# schematic_final_v3.net
KiCad netlist of a schematic drawn in EAGLE
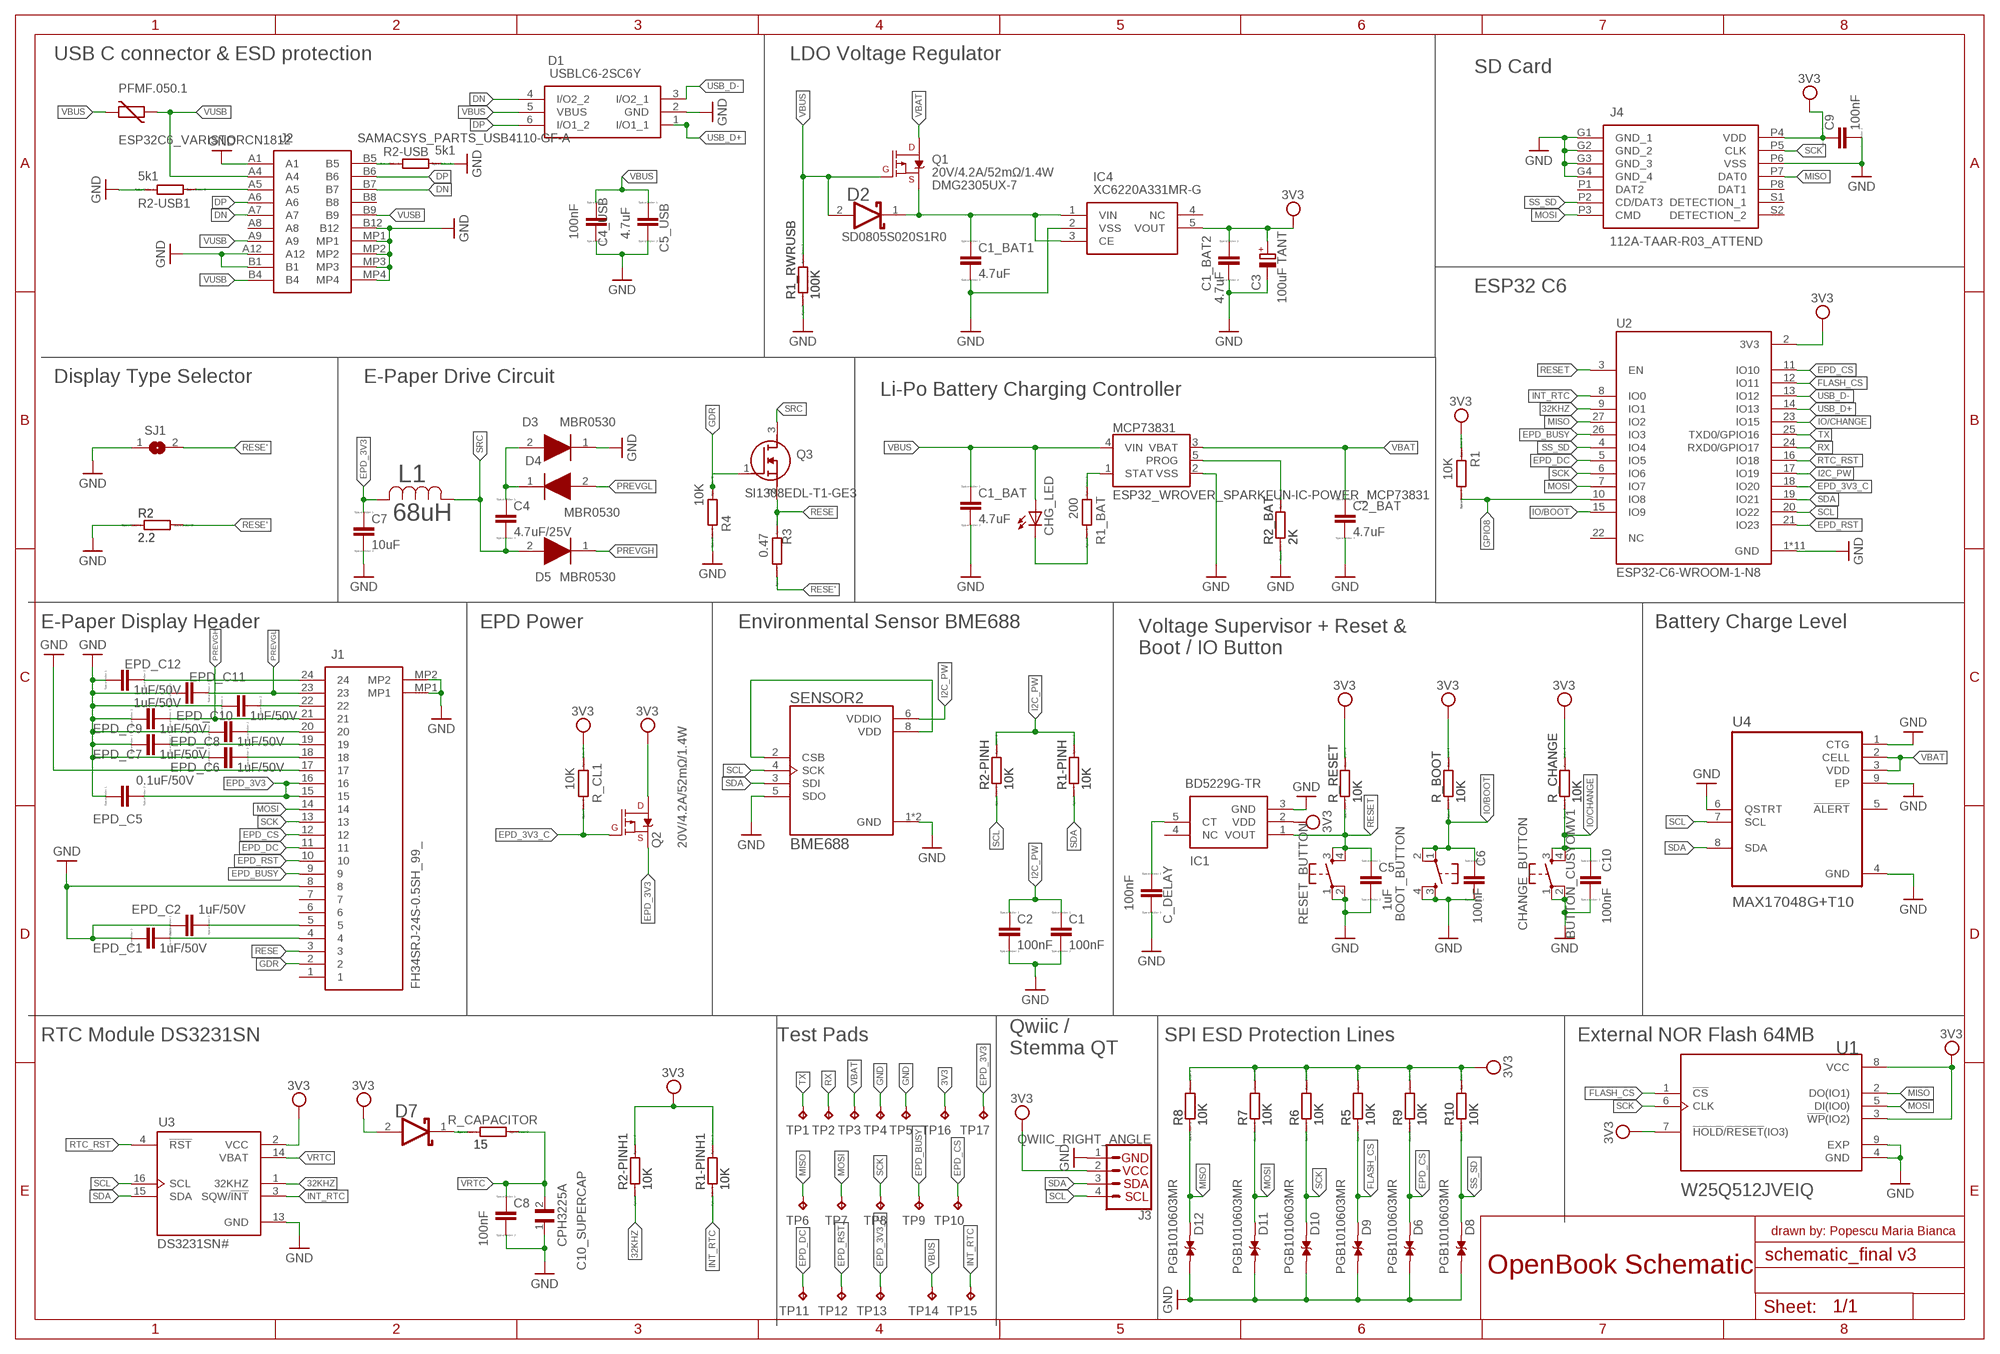
[diagram p0: schematic, sheet 1]

(export (version "E")
  (design (tool "Eeschema 10.0.6"))
  (components
    (comp (ref "BOOT_BUTTON")
      (value "BUTTON_CUSYOMV1")
      (footprint "eagle-import:MYBUTTON")
      (libsource (lib "eagle-import") (part "BUTTON_CUSYOMV1"))
    )
    (comp (ref "C1")
      (value "100nF")
      (footprint "eagle-import:EAGLE-LTSPICE_C0402")
      (libsource (lib "eagle-import") (part "EAGLE-LTSPICE_CC0402"))
    )
    (comp (ref "C1_BAT")
      (value "4.7uF")
      (footprint "eagle-import:EAGLE-LTSPICE_C0402")
      (libsource (lib "eagle-import") (part "EAGLE-LTSPICE_CC0402"))
    )
    (comp (ref "C1_BAT1")
      (value "4.7uF")
      (footprint "eagle-import:EAGLE-LTSPICE_C0402")
      (libsource (lib "eagle-import") (part "EAGLE-LTSPICE_CC0402"))
    )
    (comp (ref "C1_BAT2")
      (value "4.7uF")
      (footprint "eagle-import:EAGLE-LTSPICE_C0402")
      (libsource (lib "eagle-import") (part "EAGLE-LTSPICE_CC0402"))
    )
    (comp (ref "C2")
      (value "100nF")
      (footprint "eagle-import:EAGLE-LTSPICE_C0402")
      (libsource (lib "eagle-import") (part "EAGLE-LTSPICE_CC0402"))
    )
    (comp (ref "C2_BAT")
      (value "4.7uF")
      (footprint "eagle-import:EAGLE-LTSPICE_C0402")
      (libsource (lib "eagle-import") (part "EAGLE-LTSPICE_CC0402"))
    )
    (comp (ref "C3")
      (value "100uF TANT")
      (footprint "eagle-import:RCL_CT3528")
      (libsource (lib "eagle-import") (part "RCL_CPOL-EUCT3528"))
    )
    (comp (ref "C4")
      (value "4.7uF/25V")
      (footprint "eagle-import:EAGLE-LTSPICE_C0402")
      (libsource (lib "eagle-import") (part "EAGLE-LTSPICE_CC0402"))
    )
    (comp (ref "C4_USB")
      (value "100nF")
      (footprint "eagle-import:EAGLE-LTSPICE_C0402")
      (libsource (lib "eagle-import") (part "EAGLE-LTSPICE_CC0402"))
    )
    (comp (ref "C5")
      (value "1uF")
      (footprint "eagle-import:EAGLE-LTSPICE_C0402")
      (libsource (lib "eagle-import") (part "EAGLE-LTSPICE_CC0402"))
    )
    (comp (ref "C5_USB")
      (value "4.7uF")
      (footprint "eagle-import:EAGLE-LTSPICE_C0402")
      (libsource (lib "eagle-import") (part "EAGLE-LTSPICE_CC0402"))
    )
    (comp (ref "C6")
      (value "100nF")
      (footprint "eagle-import:EAGLE-LTSPICE_C0402")
      (libsource (lib "eagle-import") (part "EAGLE-LTSPICE_CC0402"))
    )
    (comp (ref "C7")
      (value "10uF")
      (footprint "eagle-import:EAGLE-LTSPICE_C0402")
      (libsource (lib "eagle-import") (part "EAGLE-LTSPICE_CC0402"))
    )
    (comp (ref "C8")
      (value "100nF")
      (footprint "eagle-import:EAGLE-LTSPICE_C0402")
      (libsource (lib "eagle-import") (part "EAGLE-LTSPICE_CC0402"))
    )
    (comp (ref "C9")
      (value "100nF")
      (footprint "eagle-import:EAGLE-LTSPICE_C0402")
      (libsource (lib "eagle-import") (part "EAGLE-LTSPICE_CC0402"))
    )
    (comp (ref "C10")
      (value "100nF")
      (footprint "eagle-import:EAGLE-LTSPICE_C0402")
      (libsource (lib "eagle-import") (part "EAGLE-LTSPICE_CC0402"))
    )
    (comp (ref "C10_SUPERCAP")
      (value "CPH3225A")
      (footprint "eagle-import:CAPCP3225X100N")
      (fields (field (name "MF") "Seiko Instruments"))
      (libsource (lib "eagle-import") (part "CPH3225A"))
    )
    (comp (ref "CHANGE_BUTTON")
      (value "BUTTON_CUSYOMV1")
      (footprint "eagle-import:MYBUTTON")
      (libsource (lib "eagle-import") (part "BUTTON_CUSYOMV1"))
    )
    (comp (ref "CHG_LED")
      (value "ADAFRUIT_LEDCHIP-LED0603")
      (footprint "eagle-import:ADAFRUIT_CHIP-LED0603")
      (libsource (lib "eagle-import") (part "ADAFRUIT_LEDCHIP-LED0603"))
    )
    (comp (ref "C_DELAY")
      (value "100nF")
      (footprint "eagle-import:EAGLE-LTSPICE_C0402")
      (libsource (lib "eagle-import") (part "EAGLE-LTSPICE_CC0402"))
    )
    (comp (ref "D1")
      (value "USBLC6-2SC6Y")
      (footprint "eagle-import:SOT95P280X145-6N")
      (fields (field (name "MF") "STMicroelectronics"))
      (libsource (lib "eagle-import") (part "USBLC6-2SC6Y"))
    )
    (comp (ref "D2")
      (value "SD0805S020S1R0")
      (footprint "eagle-import:ESP32_WROVER_AVX---SD0805S020S1R0_AVX_SD0805S020S1R0_0")
      (fields
        (field (name "DIGIKEY_PART_NUMBER") "478-7800-1-ND")
        (field (name "MF") "AVX")
        (field (name "MOUSER_PART_NUMBER") "581-SD0805S020S1R0")
        (field (name "ATTR") "SD0805S020S1R0")
      )
      (libsource (lib "eagle-import") (part "ESP32_WROVER_AVX---SD0805S020S1R0_AVX_SD0805S020S1R0_0_0AVX_SD0805S020S1R0_0_0"))
    )
    (comp (ref "D3")
      (value "MBR0530")
      (footprint "eagle-import:SOD3716X135N")
      (fields (field (name "MF") "ON Semiconductor"))
      (libsource (lib "eagle-import") (part "MBR0530"))
    )
    (comp (ref "D4")
      (value "MBR0530")
      (footprint "eagle-import:SOD3716X135N")
      (fields (field (name "MF") "ON Semiconductor"))
      (libsource (lib "eagle-import") (part "MBR0530"))
    )
    (comp (ref "D5")
      (value "MBR0530")
      (footprint "eagle-import:SOD3716X135N")
      (fields (field (name "MF") "ON Semiconductor"))
      (libsource (lib "eagle-import") (part "MBR0530"))
    )
    (comp (ref "D6")
      (value "PGB1010603MR")
      (footprint "eagle-import:DIOC1608X36N")
      (fields (field (name "MF") "Littelfuse Inc."))
      (libsource (lib "eagle-import") (part "PGB1010603MR"))
    )
    (comp (ref "D7")
      (value "ESP32_WROVER_AVX---SD0805S020S1R0_AVX_SD0805S020S1R0_0_0AVX_SD0805S020S1R0_0_0")
      (footprint "eagle-import:ESP32_WROVER_AVX---SD0805S020S1R0_AVX_SD0805S020S1R0_0")
      (fields
        (field (name "DIGIKEY_PART_NUMBER") "478-7800-1-ND")
        (field (name "MF") "AVX")
        (field (name "MOUSER_PART_NUMBER") "581-SD0805S020S1R0")
      )
      (libsource (lib "eagle-import") (part "ESP32_WROVER_AVX---SD0805S020S1R0_AVX_SD0805S020S1R0_0_0AVX_SD0805S020S1R0_0_0"))
    )
    (comp (ref "D8")
      (value "PGB1010603MR")
      (footprint "eagle-import:DIOC1608X36N")
      (fields (field (name "MF") "Littelfuse Inc."))
      (libsource (lib "eagle-import") (part "PGB1010603MR"))
    )
    (comp (ref "D9")
      (value "PGB1010603MR")
      (footprint "eagle-import:DIOC1608X36N")
      (fields (field (name "MF") "Littelfuse Inc."))
      (libsource (lib "eagle-import") (part "PGB1010603MR"))
    )
    (comp (ref "D10")
      (value "PGB1010603MR")
      (footprint "eagle-import:DIOC1608X36N")
      (fields (field (name "MF") "Littelfuse Inc."))
      (libsource (lib "eagle-import") (part "PGB1010603MR"))
    )
    (comp (ref "D11")
      (value "PGB1010603MR")
      (footprint "eagle-import:DIOC1608X36N")
      (fields (field (name "MF") "Littelfuse Inc."))
      (libsource (lib "eagle-import") (part "PGB1010603MR"))
    )
    (comp (ref "D12")
      (value "PGB1010603MR")
      (footprint "eagle-import:DIOC1608X36N")
      (fields (field (name "MF") "Littelfuse Inc."))
      (libsource (lib "eagle-import") (part "PGB1010603MR"))
    )
    (comp (ref "EPD_C1")
      (value "1uF/50V")
      (footprint "eagle-import:EAGLE-LTSPICE_C0402")
      (libsource (lib "eagle-import") (part "EAGLE-LTSPICE_CC0402"))
    )
    (comp (ref "EPD_C2")
      (value "1uF/50V")
      (footprint "eagle-import:EAGLE-LTSPICE_C0402")
      (libsource (lib "eagle-import") (part "EAGLE-LTSPICE_CC0402"))
    )
    (comp (ref "EPD_C5")
      (value "0.1uF/50V")
      (footprint "eagle-import:EAGLE-LTSPICE_C0402")
      (libsource (lib "eagle-import") (part "EAGLE-LTSPICE_CC0402"))
    )
    (comp (ref "EPD_C6")
      (value "1uF/50V")
      (footprint "eagle-import:EAGLE-LTSPICE_C0402")
      (libsource (lib "eagle-import") (part "EAGLE-LTSPICE_CC0402"))
    )
    (comp (ref "EPD_C7")
      (value "1uF/50V")
      (footprint "eagle-import:EAGLE-LTSPICE_C0402")
      (libsource (lib "eagle-import") (part "EAGLE-LTSPICE_CC0402"))
    )
    (comp (ref "EPD_C8")
      (value "1uF/50V")
      (footprint "eagle-import:EAGLE-LTSPICE_C0402")
      (libsource (lib "eagle-import") (part "EAGLE-LTSPICE_CC0402"))
    )
    (comp (ref "EPD_C9")
      (value "1uF/50V")
      (footprint "eagle-import:EAGLE-LTSPICE_C0402")
      (libsource (lib "eagle-import") (part "EAGLE-LTSPICE_CC0402"))
    )
    (comp (ref "EPD_C10")
      (value "1uF/50V")
      (footprint "eagle-import:EAGLE-LTSPICE_C0402")
      (libsource (lib "eagle-import") (part "EAGLE-LTSPICE_CC0402"))
    )
    (comp (ref "EPD_C11")
      (value "1uF/50V")
      (footprint "eagle-import:EAGLE-LTSPICE_C0402")
      (libsource (lib "eagle-import") (part "EAGLE-LTSPICE_CC0402"))
    )
    (comp (ref "EPD_C12")
      (value "1uF/50V")
      (footprint "eagle-import:EAGLE-LTSPICE_C0402")
      (libsource (lib "eagle-import") (part "EAGLE-LTSPICE_CC0402"))
    )
    (comp (ref "IC1")
      (value "BD5229G-TR")
      (footprint "eagle-import:SOT95P280X125-5N")
      (fields (field (name "MOUSER_PART_NUMBER") "755-BD5229G-TR"))
      (libsource (lib "eagle-import") (part "BD5229G-TR"))
    )
    (comp (ref "IC4")
      (value "XC6220A331MR-G")
      (footprint "eagle-import:SOT95P280X120-5N")
      (fields (field (name "MOUSER_PART_NUMBER") "865-XC6220A331MR-G"))
      (libsource (lib "eagle-import") (part "XC6220A331MR-G"))
    )
    (comp (ref "J1")
      (value "FH34SRJ-24S-0.5SH_99_")
      (footprint "eagle-import:FH34SRJ24S05SH99")
      (fields
        (field (name "MANUFACTURER_PART_NUMBER") "FH34SRJ-24S-0.5SH(99)")
        (field (name "MOUSER_PART_NUMBER") "798-FH34SRJ24S05SH99")
      )
      (libsource (lib "eagle-import") (part "FH34SRJ-24S-0.5SH_99_"))
    )
    (comp (ref "J2")
      (value "SAMACSYS_PARTS_USB4110-GF-A")
      (footprint "eagle-import:SAMACSYS_PARTS_USB4110GFA")
      (fields
        (field (name "MANUFACTURER_PART_NUMBER") "USB4110-GF-A")
        (field (name "MOUSER_PART_NUMBER") "640-USB4110-GF-A")
      )
      (libsource (lib "eagle-import") (part "SAMACSYS_PARTS_USB4110-GF-A"))
    )
    (comp (ref "J3")
      (value "QWIIC_RIGHT_ANGLE")
      (footprint "eagle-import:JST04_1MM_RA")
      (libsource (lib "eagle-import") (part "QWIIC_CONNECTORJS-1MM"))
    )
    (comp (ref "J4")
      (value "112A-TAAR-R03_ATTEND")
      (footprint "eagle-import:112ATAARR03ATTEND")
      (fields (field (name "MANUFACTURER_PART_NUMBER") "112A-TAAR-R03 ATTEND"))
      (libsource (lib "eagle-import") (part "112A-TAAR-R03_ATTEND"))
    )
    (comp (ref "L1")
      (value "68uH")
      (footprint "eagle-import:IND_4828-WE-TPC_WRE")
      (fields
        (field (name "MANUFACTURER_PART_NUMBER") "744043680")
        (field (name "COPYRIGHT") "Copyright (C) 2024 Ultra Librarian. All rights reserved.")
      )
      (libsource (lib "eagle-import") (part "744043680IND_4828-WE-TPC_WRE"))
    )
    (comp (ref "MCP73831")
      (value "ESP32_WROVER_SPARKFUN-IC-POWER_MCP73831")
      (footprint "eagle-import:ESP32_WROVER_SPARKFUN-IC-POWER_SOT23-5")
      (libsource (lib "eagle-import") (part "ESP32_WROVER_SPARKFUN-IC-POWER_MCP73831"))
    )
    (comp (ref "PFMF.050.1")
      (value "ESP32C6_VARISTORCN1812")
      (footprint "eagle-import:ESP32C6_VARISTOR_CT_CN1812")
      (libsource (lib "eagle-import") (part "ESP32C6_VARISTORCN1812"))
    )
    (comp (ref "Q1")
      (value "20V/4.2A/52mΩ/1.4W")
      (footprint "eagle-import:ESP32_WROVER_SPARKFUN-DISCRETESEMI_SOT23-3")
      (fields (field (name "ATTR") "DMG2305UX-7"))
      (libsource (lib "eagle-import") (part "ESP32_WROVER_SPARKFUN-DISCRETESEMI_MOSFET_PCH-DMG2305UX-7"))
    )
    (comp (ref "Q2")
      (value "20V/4.2A/52mΩ/1.4W")
      (footprint "eagle-import:ESP32_WROVER_SPARKFUN-DISCRETESEMI_SOT23-3")
      (libsource (lib "eagle-import") (part "ESP32_WROVER_SPARKFUN-DISCRETESEMI_MOSFET_PCH-DMG2305UX-7"))
    )
    (comp (ref "Q3")
      (value "SI1308EDL-T1-GE3")
      (footprint "eagle-import:SOT65P210X110-3N")
      (fields (field (name "MF") "Vishay Siliconix"))
      (libsource (lib "eagle-import") (part "SI1308EDL-T1-GE3"))
    )
    (comp (ref "R1")
      (value "10K")
      (footprint "eagle-import:ESP32_WROVER_EAGLE-LTSPICE_R0402")
      (libsource (lib "eagle-import") (part "ESP32_WROVER_EAGLE-LTSPICE_RR0402"))
    )
    (comp (ref "R1-PINH")
      (value "10K")
      (footprint "eagle-import:ESP32_WROVER_EAGLE-LTSPICE_R0402")
      (libsource (lib "eagle-import") (part "ESP32_WROVER_EAGLE-LTSPICE_RR0402"))
    )
    (comp (ref "R1-PINH1")
      (value "10K")
      (footprint "eagle-import:ESP32_WROVER_EAGLE-LTSPICE_R0402")
      (libsource (lib "eagle-import") (part "ESP32_WROVER_EAGLE-LTSPICE_RR0402"))
    )
    (comp (ref "R1_BAT")
      (value "200")
      (footprint "eagle-import:ESP32_WROVER_EAGLE-LTSPICE_R0402")
      (libsource (lib "eagle-import") (part "ESP32_WROVER_EAGLE-LTSPICE_RR0402"))
    )
    (comp (ref "R1_RWRUSB")
      (value "100K")
      (footprint "eagle-import:ESP32_WROVER_EAGLE-LTSPICE_R0402")
      (libsource (lib "eagle-import") (part "ESP32_WROVER_EAGLE-LTSPICE_RR0402"))
    )
    (comp (ref "R2")
      (value "2.2")
      (footprint "eagle-import:ESP32_WROVER_EAGLE-LTSPICE_R0402")
      (libsource (lib "eagle-import") (part "ESP32_WROVER_EAGLE-LTSPICE_RR0402"))
    )
    (comp (ref "R2-PINH")
      (value "10K")
      (footprint "eagle-import:ESP32_WROVER_EAGLE-LTSPICE_R0402")
      (libsource (lib "eagle-import") (part "ESP32_WROVER_EAGLE-LTSPICE_RR0402"))
    )
    (comp (ref "R2-PINH1")
      (value "10K")
      (footprint "eagle-import:ESP32_WROVER_EAGLE-LTSPICE_R0402")
      (libsource (lib "eagle-import") (part "ESP32_WROVER_EAGLE-LTSPICE_RR0402"))
    )
    (comp (ref "R2-USB")
      (value "5k1")
      (footprint "eagle-import:ESP32_WROVER_EAGLE-LTSPICE_R0402")
      (libsource (lib "eagle-import") (part "ESP32_WROVER_EAGLE-LTSPICE_RR0402"))
    )
    (comp (ref "R2-USB1")
      (value "5k1")
      (footprint "eagle-import:ESP32_WROVER_EAGLE-LTSPICE_R0402")
      (libsource (lib "eagle-import") (part "ESP32_WROVER_EAGLE-LTSPICE_RR0402"))
    )
    (comp (ref "R2_BAT")
      (value "2K")
      (footprint "eagle-import:ESP32_WROVER_EAGLE-LTSPICE_R0402")
      (libsource (lib "eagle-import") (part "ESP32_WROVER_EAGLE-LTSPICE_RR0402"))
    )
    (comp (ref "R3")
      (value "0.47")
      (footprint "eagle-import:ESP32_WROVER_EAGLE-LTSPICE_R0402")
      (libsource (lib "eagle-import") (part "ESP32_WROVER_EAGLE-LTSPICE_RR0402"))
    )
    (comp (ref "R4")
      (value "10K")
      (footprint "eagle-import:ESP32_WROVER_EAGLE-LTSPICE_R0402")
      (libsource (lib "eagle-import") (part "ESP32_WROVER_EAGLE-LTSPICE_RR0402"))
    )
    (comp (ref "R5")
      (value "10K")
      (footprint "eagle-import:ESP32_WROVER_EAGLE-LTSPICE_R0402")
      (libsource (lib "eagle-import") (part "ESP32_WROVER_EAGLE-LTSPICE_RR0402"))
    )
    (comp (ref "R6")
      (value "10K")
      (footprint "eagle-import:ESP32_WROVER_EAGLE-LTSPICE_R0402")
      (libsource (lib "eagle-import") (part "ESP32_WROVER_EAGLE-LTSPICE_RR0402"))
    )
    (comp (ref "R7")
      (value "10K")
      (footprint "eagle-import:ESP32_WROVER_EAGLE-LTSPICE_R0402")
      (libsource (lib "eagle-import") (part "ESP32_WROVER_EAGLE-LTSPICE_RR0402"))
    )
    (comp (ref "R8")
      (value "10K")
      (footprint "eagle-import:ESP32_WROVER_EAGLE-LTSPICE_R0402")
      (libsource (lib "eagle-import") (part "ESP32_WROVER_EAGLE-LTSPICE_RR0402"))
    )
    (comp (ref "R9")
      (value "10K")
      (footprint "eagle-import:ESP32_WROVER_EAGLE-LTSPICE_R0402")
      (libsource (lib "eagle-import") (part "ESP32_WROVER_EAGLE-LTSPICE_RR0402"))
    )
    (comp (ref "R10")
      (value "10K")
      (footprint "eagle-import:ESP32_WROVER_EAGLE-LTSPICE_R0402")
      (libsource (lib "eagle-import") (part "ESP32_WROVER_EAGLE-LTSPICE_RR0402"))
    )
    (comp (ref "RESET_BUTTON")
      (value "RESET_BUTTON")
      (footprint "eagle-import:MYBUTTON")
      (libsource (lib "eagle-import") (part "BUTTON_CUSYOMV1"))
    )
    (comp (ref "R_BOOT")
      (value "10K")
      (footprint "eagle-import:ESP32_WROVER_EAGLE-LTSPICE_R0402")
      (libsource (lib "eagle-import") (part "ESP32_WROVER_EAGLE-LTSPICE_RR0402"))
    )
    (comp (ref "R_CAPACITOR")
      (value "15")
      (footprint "eagle-import:ESP32_WROVER_EAGLE-LTSPICE_R0402")
      (libsource (lib "eagle-import") (part "ESP32_WROVER_EAGLE-LTSPICE_RR0402"))
    )
    (comp (ref "R_CHANGE")
      (value "10K")
      (footprint "eagle-import:ESP32_WROVER_EAGLE-LTSPICE_R0402")
      (libsource (lib "eagle-import") (part "ESP32_WROVER_EAGLE-LTSPICE_RR0402"))
    )
    (comp (ref "R_CL1")
      (value "10K")
      (footprint "eagle-import:ESP32_WROVER_EAGLE-LTSPICE_R0402")
      (libsource (lib "eagle-import") (part "ESP32_WROVER_EAGLE-LTSPICE_RR0402"))
    )
    (comp (ref "R_RESET")
      (value "10K")
      (footprint "eagle-import:ESP32_WROVER_EAGLE-LTSPICE_R0402")
      (libsource (lib "eagle-import") (part "ESP32_WROVER_EAGLE-LTSPICE_RR0402"))
    )
    (comp (ref "SENSOR2")
      (value "BME688")
      (footprint "eagle-import:ESP32_WROVER_BME680_PSON80P300X300X100-8N")
      (fields (field (name "MF") "Bosch Sensortec") (field (name "MP") "BME680"))
      (libsource (lib "eagle-import") (part "ESP32_WROVER_BME680_BME680"))
    )
    (comp (ref "SJ1") (value "SJ") (footprint "eagle-import:SJ") (libsource (lib "eagle-import") (part "SJ")))
    (comp (ref "TP1")
      (value "TPTP20R")
      (footprint "eagle-import:TP20R")
      (libsource (lib "eagle-import") (part "TPTP20R"))
    )
    (comp (ref "TP2")
      (value "TPTP20R")
      (footprint "eagle-import:TP20R")
      (libsource (lib "eagle-import") (part "TPTP20R"))
    )
    (comp (ref "TP3")
      (value "TPTP20R")
      (footprint "eagle-import:TP20R")
      (libsource (lib "eagle-import") (part "TPTP20R"))
    )
    (comp (ref "TP4")
      (value "TPTP20R")
      (footprint "eagle-import:TP20R")
      (libsource (lib "eagle-import") (part "TPTP20R"))
    )
    (comp (ref "TP5")
      (value "TPTP20R")
      (footprint "eagle-import:TP20R")
      (libsource (lib "eagle-import") (part "TPTP20R"))
    )
    (comp (ref "TP6")
      (value "TPTP20R")
      (footprint "eagle-import:TP20R")
      (libsource (lib "eagle-import") (part "TPTP20R"))
    )
    (comp (ref "TP7")
      (value "TPTP20R")
      (footprint "eagle-import:TP20R")
      (libsource (lib "eagle-import") (part "TPTP20R"))
    )
    (comp (ref "TP8")
      (value "TPTP20R")
      (footprint "eagle-import:TP20R")
      (libsource (lib "eagle-import") (part "TPTP20R"))
    )
    (comp (ref "TP9")
      (value "TPTP20R")
      (footprint "eagle-import:TP20R")
      (libsource (lib "eagle-import") (part "TPTP20R"))
    )
    (comp (ref "TP10")
      (value "TPTP20R")
      (footprint "eagle-import:TP20R")
      (libsource (lib "eagle-import") (part "TPTP20R"))
    )
    (comp (ref "TP11")
      (value "TPTP20R")
      (footprint "eagle-import:TP20R")
      (libsource (lib "eagle-import") (part "TPTP20R"))
    )
    (comp (ref "TP12")
      (value "TPTP20R")
      (footprint "eagle-import:TP20R")
      (libsource (lib "eagle-import") (part "TPTP20R"))
    )
    (comp (ref "TP13")
      (value "TPTP20R")
      (footprint "eagle-import:TP20R")
      (libsource (lib "eagle-import") (part "TPTP20R"))
    )
    (comp (ref "TP14")
      (value "TPTP20R")
      (footprint "eagle-import:TP20R")
      (libsource (lib "eagle-import") (part "TPTP20R"))
    )
    (comp (ref "TP15")
      (value "TPTP20R")
      (footprint "eagle-import:TP20R")
      (libsource (lib "eagle-import") (part "TPTP20R"))
    )
    (comp (ref "TP16")
      (value "TPTP20R")
      (footprint "eagle-import:TP20R")
      (libsource (lib "eagle-import") (part "TPTP20R"))
    )
    (comp (ref "TP17")
      (value "TPTP20R")
      (footprint "eagle-import:TP20R")
      (libsource (lib "eagle-import") (part "TPTP20R"))
    )
    (comp (ref "U1")
      (value "W25Q512JVEIQ")
      (footprint "eagle-import:SON127P600X800X80-9N")
      (fields (field (name "MF") "Winbond Electronics"))
      (libsource (lib "eagle-import") (part "W25Q512JVEIQ"))
    )
    (comp (ref "U2")
      (value "ESP32-C6-WROOM-1-N8")
      (footprint "eagle-import:XCVR_ESP32-C6-WROOM-1-N8")
      (fields (field (name "MF") "Espressif Systems"))
      (libsource (lib "eagle-import") (part "ESP32-C6-WROOM-1-N8"))
    )
    (comp (ref "U3")
      (value "DS3231SN#")
      (footprint "eagle-import:SOIC127P1032X265-16N")
      (fields (field (name "MF") "Analog Devices"))
      (libsource (lib "eagle-import") (part "DS3231SN#"))
    )
    (comp (ref "U4")
      (value "MAX17048G+T10")
      (footprint "eagle-import:SON50P200X200X80-9N")
      (fields (field (name "MF") "Analog Devices"))
      (libsource (lib "eagle-import") (part "MAX17048G+T10"))
    )
  )
  (nets
    (net (code "1") (name "3V3") (class "Default")
      (node (ref "C1_BAT2") (pin "1") (pinfunction "1_1") (pintype "passive"))
      (node (ref "C3") (pin "+") (pinfunction "+_+") (pintype "passive"))
      (node (ref "C9") (pin "1") (pinfunction "1_1") (pintype "passive"))
      (node (ref "D7") (pin "2") (pinfunction "ANODE_2") (pintype "bidirectional"))
      (node (ref "IC1") (pin "2") (pinfunction "VDD_2") (pintype "bidirectional"))
      (node (ref "IC4") (pin "5") (pinfunction "VOUT_5") (pintype "bidirectional"))
      (node (ref "J3") (pin "2") (pinfunction "2_2") (pintype "power_in"))
      (node (ref "J4") (pin "P4") (pinfunction "VDD_P4") (pintype "bidirectional"))
      (node (ref "Q2") (pin "3") (pinfunction "D_3") (pintype "bidirectional"))
      (node (ref "R1") (pin "2") (pinfunction "2_2") (pintype "passive"))
      (node (ref "R1-PINH1") (pin "2") (pinfunction "2_2") (pintype "passive"))
      (node (ref "R10") (pin "2") (pinfunction "2_2") (pintype "passive"))
      (node (ref "R2-PINH1") (pin "2") (pinfunction "2_2") (pintype "passive"))
      (node (ref "R5") (pin "2") (pinfunction "2_2") (pintype "passive"))
      (node (ref "R6") (pin "2") (pinfunction "2_2") (pintype "passive"))
      (node (ref "R7") (pin "2") (pinfunction "2_2") (pintype "passive"))
      (node (ref "R8") (pin "2") (pinfunction "2_2") (pintype "passive"))
      (node (ref "R9") (pin "2") (pinfunction "2_2") (pintype "passive"))
      (node (ref "R_BOOT") (pin "2") (pinfunction "2_2") (pintype "passive"))
      (node (ref "R_CHANGE") (pin "2") (pinfunction "2_2") (pintype "passive"))
      (node (ref "R_CL1") (pin "2") (pinfunction "2_2") (pintype "passive"))
      (node (ref "R_RESET") (pin "2") (pinfunction "2_2") (pintype "passive"))
      (node (ref "TP16") (pin "TP") (pinfunction "TP_TP") (pintype "input"))
      (node (ref "U1") (pin "3") (pinfunction "~{WP}(IO2)_3") (pintype "bidirectional"))
      (node (ref "U1") (pin "7") (pinfunction "~{HOLD}/~{RESET}(IO3)_7") (pintype "bidirectional"))
      (node (ref "U1") (pin "8") (pinfunction "VCC_8") (pintype "power_in"))
      (node (ref "U2") (pin "2") (pinfunction "3V3_2") (pintype "power_in"))
      (node (ref "U3") (pin "2") (pinfunction "VCC_2") (pintype "power_in"))
    )
    (net (code "2") (name "32KHZ") (class "Default")
      (node (ref "R2-PINH1") (pin "1") (pinfunction "1_1") (pintype "passive"))
      (node (ref "U2") (pin "9") (pinfunction "IO1_9") (pintype "bidirectional"))
      (node (ref "U3") (pin "1") (pinfunction "32KHZ_1") (pintype "output"))
    )
    (net (code "3") (name "DN") (class "Default")
      (node (ref "D1") (pin "4") (pinfunction "I/O2_2_4") (pintype "bidirectional"))
      (node (ref "J2") (pin "A7") (pinfunction "A7_A7") (pintype "bidirectional"))
      (node (ref "J2") (pin "B7") (pinfunction "B7_B7") (pintype "bidirectional"))
    )
    (net (code "4") (name "DP") (class "Default")
      (node (ref "D1") (pin "6") (pinfunction "I/O1_2_6") (pintype "bidirectional"))
      (node (ref "J2") (pin "A6") (pinfunction "A6_A6") (pintype "bidirectional"))
      (node (ref "J2") (pin "B6") (pinfunction "B6_B6") (pintype "bidirectional"))
    )
    (net (code "5") (name "EPD_3V3") (class "Default")
      (node (ref "C7") (pin "1") (pinfunction "1_1") (pintype "passive"))
      (node (ref "EPD_C5") (pin "2") (pinfunction "2_2") (pintype "passive"))
      (node (ref "J1") (pin "15") (pinfunction "15_15") (pintype "bidirectional"))
      (node (ref "J1") (pin "16") (pinfunction "16_16") (pintype "bidirectional"))
      (node (ref "L1") (pin "2") (pinfunction "2_2") (pintype "passive"))
      (node (ref "Q2") (pin "2") (pinfunction "S_2") (pintype "bidirectional"))
      (node (ref "TP17") (pin "TP") (pinfunction "TP_TP") (pintype "input"))
    )
    (net (code "6") (name "EPD_3V3_C") (class "Default")
      (node (ref "Q2") (pin "1") (pinfunction "G_1") (pintype "bidirectional"))
      (node (ref "R_CL1") (pin "1") (pinfunction "1_1") (pintype "passive"))
      (node (ref "TP13") (pin "TP") (pinfunction "TP_TP") (pintype "input"))
      (node (ref "U2") (pin "18") (pinfunction "IO20_18") (pintype "bidirectional"))
    )
    (net (code "7") (name "EPD_BUSY") (class "Default")
      (node (ref "J1") (pin "9") (pinfunction "9_9") (pintype "bidirectional"))
      (node (ref "TP9") (pin "TP") (pinfunction "TP_TP") (pintype "input"))
      (node (ref "U2") (pin "26") (pinfunction "IO3_26") (pintype "bidirectional"))
    )
    (net (code "8") (name "EPD_CS") (class "Default")
      (node (ref "D6") (pin "2") (pinfunction "2_2") (pintype "passive"))
      (node (ref "J1") (pin "12") (pinfunction "12_12") (pintype "bidirectional"))
      (node (ref "R9") (pin "1") (pinfunction "1_1") (pintype "passive"))
      (node (ref "TP10") (pin "TP") (pinfunction "TP_TP") (pintype "input"))
      (node (ref "U2") (pin "11") (pinfunction "IO10_11") (pintype "bidirectional"))
    )
    (net (code "9") (name "EPD_DC") (class "Default")
      (node (ref "J1") (pin "11") (pinfunction "11_11") (pintype "bidirectional"))
      (node (ref "TP11") (pin "TP") (pinfunction "TP_TP") (pintype "input"))
      (node (ref "U2") (pin "5") (pinfunction "IO5_5") (pintype "bidirectional"))
    )
    (net (code "10") (name "EPD_RST") (class "Default")
      (node (ref "J1") (pin "10") (pinfunction "10_10") (pintype "bidirectional"))
      (node (ref "TP12") (pin "TP") (pinfunction "TP_TP") (pintype "input"))
      (node (ref "U2") (pin "21") (pinfunction "IO23_21") (pintype "bidirectional"))
    )
    (net (code "11") (name "FLASH_CS") (class "Default")
      (node (ref "D9") (pin "2") (pinfunction "2_2") (pintype "passive"))
      (node (ref "R5") (pin "1") (pinfunction "1_1") (pintype "passive"))
      (node (ref "U1") (pin "1") (pinfunction "~{CS}_1") (pintype "input"))
      (node (ref "U2") (pin "12") (pinfunction "IO11_12") (pintype "bidirectional"))
    )
    (net (code "12") (name "GDR") (class "Default")
      (node (ref "J1") (pin "2") (pinfunction "2_2") (pintype "bidirectional"))
      (node (ref "Q3") (pin "1") (pinfunction "G_1") (pintype "bidirectional"))
      (node (ref "R4") (pin "2") (pinfunction "2_2") (pintype "passive"))
    )
    (net (code "13") (name "GND") (class "Default")
      (node (ref "BOOT_BUTTON") (pin "3") (pinfunction "3_3") (pintype "passive"))
      (node (ref "BOOT_BUTTON") (pin "4") (pinfunction "4_4") (pintype "passive"))
      (node (ref "C1") (pin "2") (pinfunction "2_2") (pintype "passive"))
      (node (ref "C10") (pin "2") (pinfunction "2_2") (pintype "passive"))
      (node (ref "C10_SUPERCAP") (pin "1") (pinfunction "1_1") (pintype "passive"))
      (node (ref "C1_BAT") (pin "2") (pinfunction "2_2") (pintype "passive"))
      (node (ref "C1_BAT1") (pin "2") (pinfunction "2_2") (pintype "passive"))
      (node (ref "C1_BAT2") (pin "2") (pinfunction "2_2") (pintype "passive"))
      (node (ref "C2") (pin "2") (pinfunction "2_2") (pintype "passive"))
      (node (ref "C2_BAT") (pin "2") (pinfunction "2_2") (pintype "passive"))
      (node (ref "C3") (pin "-") (pinfunction "-_-") (pintype "passive"))
      (node (ref "C4_USB") (pin "2") (pinfunction "2_2") (pintype "passive"))
      (node (ref "C5") (pin "2") (pinfunction "2_2") (pintype "passive"))
      (node (ref "C5_USB") (pin "2") (pinfunction "2_2") (pintype "passive"))
      (node (ref "C6") (pin "2") (pinfunction "2_2") (pintype "passive"))
      (node (ref "C7") (pin "2") (pinfunction "2_2") (pintype "passive"))
      (node (ref "C8") (pin "2") (pinfunction "2_2") (pintype "passive"))
      (node (ref "C9") (pin "2") (pinfunction "2_2") (pintype "passive"))
      (node (ref "CHANGE_BUTTON") (pin "1") (pinfunction "1_1") (pintype "passive"))
      (node (ref "CHANGE_BUTTON") (pin "2") (pinfunction "2_2") (pintype "passive"))
      (node (ref "C_DELAY") (pin "2") (pinfunction "2_2") (pintype "passive"))
      (node (ref "D1") (pin "2") (pinfunction "GND_2") (pintype "bidirectional"))
      (node (ref "D10") (pin "1") (pinfunction "1_1") (pintype "passive"))
      (node (ref "D11") (pin "1") (pinfunction "1_1") (pintype "passive"))
      (node (ref "D12") (pin "1") (pinfunction "1_1") (pintype "passive"))
      (node (ref "D3") (pin "1") (pinfunction "K_1") (pintype "bidirectional"))
      (node (ref "D6") (pin "1") (pinfunction "1_1") (pintype "passive"))
      (node (ref "D8") (pin "1") (pinfunction "1_1") (pintype "passive"))
      (node (ref "D9") (pin "1") (pinfunction "1_1") (pintype "passive"))
      (node (ref "EPD_C1") (pin "1") (pinfunction "1_1") (pintype "passive"))
      (node (ref "EPD_C10") (pin "1") (pinfunction "1_1") (pintype "passive"))
      (node (ref "EPD_C11") (pin "1") (pinfunction "1_1") (pintype "passive"))
      (node (ref "EPD_C12") (pin "1") (pinfunction "1_1") (pintype "passive"))
      (node (ref "EPD_C2") (pin "1") (pinfunction "1_1") (pintype "passive"))
      (node (ref "EPD_C5") (pin "1") (pinfunction "1_1") (pintype "passive"))
      (node (ref "EPD_C6") (pin "1") (pinfunction "1_1") (pintype "passive"))
      (node (ref "EPD_C7") (pin "1") (pinfunction "1_1") (pintype "passive"))
      (node (ref "EPD_C8") (pin "1") (pinfunction "1_1") (pintype "passive"))
      (node (ref "EPD_C9") (pin "1") (pinfunction "1_1") (pintype "passive"))
      (node (ref "IC1") (pin "3") (pinfunction "GND_3") (pintype "bidirectional"))
      (node (ref "IC4") (pin "2") (pinfunction "VSS_2") (pintype "bidirectional"))
      (node (ref "J1") (pin "17") (pinfunction "17_17") (pintype "bidirectional"))
      (node (ref "J1") (pin "8") (pinfunction "8_8") (pintype "bidirectional"))
      (node (ref "J1") (pin "MP1") (pinfunction "MP1_MP1") (pintype "bidirectional"))
      (node (ref "J1") (pin "MP2") (pinfunction "MP2_MP2") (pintype "bidirectional"))
      (node (ref "J2") (pin "A1") (pinfunction "A1_A1") (pintype "bidirectional"))
      (node (ref "J2") (pin "A12") (pinfunction "A12_A12") (pintype "bidirectional"))
      (node (ref "J2") (pin "B1") (pinfunction "B1_B1") (pintype "bidirectional"))
      (node (ref "J2") (pin "B12") (pinfunction "B12_B12") (pintype "bidirectional"))
      (node (ref "J2") (pin "MP1") (pinfunction "MP1_MP1") (pintype "bidirectional"))
      (node (ref "J2") (pin "MP2") (pinfunction "MP2_MP2") (pintype "bidirectional"))
      (node (ref "J2") (pin "MP3") (pinfunction "MP3_MP3") (pintype "bidirectional"))
      (node (ref "J2") (pin "MP4") (pinfunction "MP4_MP4") (pintype "bidirectional"))
      (node (ref "J3") (pin "1") (pinfunction "1_1") (pintype "power_in"))
      (node (ref "J4") (pin "G1") (pinfunction "GND_1_G1") (pintype "bidirectional"))
      (node (ref "J4") (pin "G2") (pinfunction "GND_2_G2") (pintype "bidirectional"))
      (node (ref "J4") (pin "G3") (pinfunction "GND_3_G3") (pintype "bidirectional"))
      (node (ref "J4") (pin "G4") (pinfunction "GND_4_G4") (pintype "bidirectional"))
      (node (ref "J4") (pin "P6") (pinfunction "VSS_P6") (pintype "bidirectional"))
      (node (ref "MCP73831") (pin "2") (pinfunction "VSS_2") (pintype "power_in"))
      (node (ref "R1_RWRUSB") (pin "1") (pinfunction "1_1") (pintype "passive"))
      (node (ref "R2") (pin "1") (pinfunction "1_1") (pintype "passive"))
      (node (ref "R2-USB") (pin "2") (pinfunction "2_2") (pintype "passive"))
      (node (ref "R2-USB1") (pin "1") (pinfunction "1_1") (pintype "passive"))
      (node (ref "R2_BAT") (pin "1") (pinfunction "1_1") (pintype "passive"))
      (node (ref "R4") (pin "1") (pinfunction "1_1") (pintype "passive"))
      (node (ref "RESET_BUTTON") (pin "1") (pinfunction "1_1") (pintype "passive"))
      (node (ref "RESET_BUTTON") (pin "2") (pinfunction "2_2") (pintype "passive"))
      (node (ref "SENSOR2") (pin "1") (pinfunction "GND_1") (pintype "power_in"))
      (node (ref "SENSOR2") (pin "5") (pinfunction "SDO_5") (pintype "bidirectional"))
      (node (ref "SENSOR2") (pin "7") (pinfunction "GND_7") (pintype "power_in"))
      (node (ref "SJ1") (pin "1") (pinfunction "1_1") (pintype "passive"))
      (node (ref "TP4") (pin "TP") (pinfunction "TP_TP") (pintype "input"))
      (node (ref "TP5") (pin "TP") (pinfunction "TP_TP") (pintype "input"))
      (node (ref "U1") (pin "4") (pinfunction "GND_4") (pintype "power_in"))
      (node (ref "U1") (pin "9") (pinfunction "EXP_9") (pintype "passive"))
      (node (ref "U2") (pin "1") (pinfunction "GND_1") (pintype "power_in"))
      (node (ref "U2") (pin "28") (pinfunction "GND_28") (pintype "power_in"))
      (node (ref "U2") (pin "29_1") (pinfunction "GND_29_1") (pintype "power_in"))
      (node (ref "U2") (pin "29_2") (pinfunction "GND_29_2") (pintype "power_in"))
      (node (ref "U2") (pin "29_3") (pinfunction "GND_29_3") (pintype "power_in"))
      (node (ref "U2") (pin "29_4") (pinfunction "GND_29_4") (pintype "power_in"))
      (node (ref "U2") (pin "29_5") (pinfunction "GND_29_5") (pintype "power_in"))
      (node (ref "U2") (pin "29_6") (pinfunction "GND_29_6") (pintype "power_in"))
      (node (ref "U2") (pin "29_7") (pinfunction "GND_29_7") (pintype "power_in"))
      (node (ref "U2") (pin "29_8") (pinfunction "GND_29_8") (pintype "power_in"))
      (node (ref "U2") (pin "29_9") (pinfunction "GND_29_9") (pintype "power_in"))
      (node (ref "U3") (pin "13") (pinfunction "GND_13") (pintype "power_in"))
      (node (ref "U4") (pin "1") (pinfunction "CTG_1") (pintype "power_in"))
      (node (ref "U4") (pin "4") (pinfunction "GND_4") (pintype "power_in"))
      (node (ref "U4") (pin "6") (pinfunction "QSTRT_6") (pintype "input"))
      (node (ref "U4") (pin "9") (pinfunction "EP_9") (pintype "power_in"))
    )
    (net (code "14") (name "GPIO8") (class "Default")
      (node (ref "R1") (pin "1") (pinfunction "1_1") (pintype "passive"))
      (node (ref "U2") (pin "10") (pinfunction "IO8_10") (pintype "bidirectional"))
    )
    (net (code "15") (name "I2C_PW") (class "Default")
      (node (ref "C1") (pin "1") (pinfunction "1_1") (pintype "passive"))
      (node (ref "C2") (pin "1") (pinfunction "1_1") (pintype "passive"))
      (node (ref "R1-PINH") (pin "2") (pinfunction "2_2") (pintype "passive"))
      (node (ref "R2-PINH") (pin "2") (pinfunction "2_2") (pintype "passive"))
      (node (ref "SENSOR2") (pin "6") (pinfunction "VDDIO_6") (pintype "power_in"))
      (node (ref "U2") (pin "17") (pinfunction "IO19_17") (pintype "bidirectional"))
    )
    (net (code "16") (name "INT_RTC") (class "Default")
      (node (ref "R1-PINH1") (pin "1") (pinfunction "1_1") (pintype "passive"))
      (node (ref "TP15") (pin "TP") (pinfunction "TP_TP") (pintype "input"))
      (node (ref "U2") (pin "8") (pinfunction "IO0_8") (pintype "bidirectional"))
      (node (ref "U3") (pin "3") (pinfunction "SQW/~{INT}_3") (pintype "output"))
    )
    (net (code "17") (name "IO{slash}BOOT") (class "Default")
      (node (ref "BOOT_BUTTON") (pin "1") (pinfunction "1_1") (pintype "passive"))
      (node (ref "BOOT_BUTTON") (pin "2") (pinfunction "2_2") (pintype "passive"))
      (node (ref "C6") (pin "1") (pinfunction "1_1") (pintype "passive"))
      (node (ref "R_BOOT") (pin "1") (pinfunction "1_1") (pintype "passive"))
      (node (ref "U2") (pin "15") (pinfunction "IO9_15") (pintype "bidirectional"))
    )
    (net (code "18") (name "IO{slash}CHANGE") (class "Default")
      (node (ref "C10") (pin "1") (pinfunction "1_1") (pintype "passive"))
      (node (ref "CHANGE_BUTTON") (pin "3") (pinfunction "3_3") (pintype "passive"))
      (node (ref "CHANGE_BUTTON") (pin "4") (pinfunction "4_4") (pintype "passive"))
      (node (ref "R_CHANGE") (pin "1") (pinfunction "1_1") (pintype "passive"))
      (node (ref "U2") (pin "23") (pinfunction "IO15_23") (pintype "bidirectional"))
    )
    (net (code "19") (name "MISO") (class "Default")
      (node (ref "D12") (pin "2") (pinfunction "2_2") (pintype "passive"))
      (node (ref "J4") (pin "P7") (pinfunction "DAT0_P7") (pintype "bidirectional"))
      (node (ref "R8") (pin "1") (pinfunction "1_1") (pintype "passive"))
      (node (ref "TP6") (pin "TP") (pinfunction "TP_TP") (pintype "input"))
      (node (ref "U1") (pin "2") (pinfunction "DO(IO1)_2") (pintype "bidirectional"))
      (node (ref "U2") (pin "27") (pinfunction "IO2_27") (pintype "bidirectional"))
    )
    (net (code "20") (name "MOSI") (class "Default")
      (node (ref "D11") (pin "2") (pinfunction "2_2") (pintype "passive"))
      (node (ref "J1") (pin "14") (pinfunction "14_14") (pintype "bidirectional"))
      (node (ref "J4") (pin "P3") (pinfunction "CMD_P3") (pintype "bidirectional"))
      (node (ref "R7") (pin "1") (pinfunction "1_1") (pintype "passive"))
      (node (ref "TP7") (pin "TP") (pinfunction "TP_TP") (pintype "input"))
      (node (ref "U1") (pin "5") (pinfunction "DI(IO0)_5") (pintype "bidirectional"))
      (node (ref "U2") (pin "7") (pinfunction "IO7_7") (pintype "bidirectional"))
    )
    (net (code "21") (name "Net-(CHG_LED-PadC)") (class "Default")
      (node (ref "CHG_LED") (pin "C") (pinfunction "C_C") (pintype "passive"))
      (node (ref "R1_BAT") (pin "1") (pinfunction "1_1") (pintype "passive"))
    )
    (net (code "22") (name "Net-(D2-ANODE)") (class "Default")
      (node (ref "D2") (pin "2") (pinfunction "ANODE_2") (pintype "bidirectional"))
      (node (ref "Q1") (pin "1") (pinfunction "G_1") (pintype "bidirectional"))
      (node (ref "R1_RWRUSB") (pin "2") (pinfunction "2_2") (pintype "passive"))
    )
    (net (code "23") (name "Net-(D2-CATHODE)") (class "Default")
      (node (ref "C1_BAT1") (pin "1") (pinfunction "1_1") (pintype "passive"))
      (node (ref "D2") (pin "1") (pinfunction "CATHODE_1") (pintype "bidirectional"))
      (node (ref "IC4") (pin "1") (pinfunction "VIN_1") (pintype "bidirectional"))
      (node (ref "IC4") (pin "3") (pinfunction "CE_3") (pintype "bidirectional"))
      (node (ref "Q1") (pin "2") (pinfunction "S_2") (pintype "bidirectional"))
    )
    (net (code "24") (name "Net-(D3-A)") (class "Default")
      (node (ref "C4") (pin "1") (pinfunction "1_1") (pintype "passive"))
      (node (ref "D3") (pin "2") (pinfunction "A_2") (pintype "bidirectional"))
      (node (ref "D4") (pin "1") (pinfunction "K_1") (pintype "bidirectional"))
    )
    (net (code "25") (name "Net-(D7-CATHODE)") (class "Default")
      (node (ref "D7") (pin "1") (pinfunction "CATHODE_1") (pintype "bidirectional"))
      (node (ref "R_CAPACITOR") (pin "1") (pinfunction "1_1") (pintype "passive"))
    )
    (net (code "26") (name "Net-(EPD_C1-Pad2)") (class "Default")
      (node (ref "EPD_C1") (pin "2") (pinfunction "2_2") (pintype "passive"))
      (node (ref "J1") (pin "4") (pinfunction "4_4") (pintype "bidirectional"))
    )
    (net (code "27") (name "Net-(EPD_C2-Pad2)") (class "Default")
      (node (ref "EPD_C2") (pin "2") (pinfunction "2_2") (pintype "passive"))
      (node (ref "J1") (pin "5") (pinfunction "5_5") (pintype "bidirectional"))
    )
    (net (code "28") (name "Net-(EPD_C6-Pad2)") (class "Default")
      (node (ref "EPD_C6") (pin "2") (pinfunction "2_2") (pintype "passive"))
      (node (ref "J1") (pin "18") (pinfunction "18_18") (pintype "bidirectional"))
    )
    (net (code "29") (name "Net-(EPD_C7-Pad2)") (class "Default")
      (node (ref "EPD_C7") (pin "2") (pinfunction "2_2") (pintype "passive"))
      (node (ref "J1") (pin "19") (pinfunction "19_19") (pintype "bidirectional"))
    )
    (net (code "30") (name "Net-(EPD_C8-Pad2)") (class "Default")
      (node (ref "EPD_C8") (pin "2") (pinfunction "2_2") (pintype "passive"))
      (node (ref "J1") (pin "20") (pinfunction "20_20") (pintype "bidirectional"))
    )
    (net (code "31") (name "Net-(EPD_C10-Pad2)") (class "Default")
      (node (ref "EPD_C10") (pin "2") (pinfunction "2_2") (pintype "passive"))
      (node (ref "J1") (pin "22") (pinfunction "22_22") (pintype "bidirectional"))
    )
    (net (code "32") (name "Net-(EPD_C12-Pad2)") (class "Default")
      (node (ref "EPD_C12") (pin "2") (pinfunction "2_2") (pintype "passive"))
      (node (ref "J1") (pin "24") (pinfunction "24_24") (pintype "bidirectional"))
    )
    (net (code "33") (name "Net-(IC1-CT)") (class "Default")
      (node (ref "C_DELAY") (pin "1") (pinfunction "1_1") (pintype "passive"))
      (node (ref "IC1") (pin "5") (pinfunction "CT_5") (pintype "bidirectional"))
    )
    (net (code "34") (name "Net-(J2-PadA5)") (class "Default")
      (node (ref "J2") (pin "A5") (pinfunction "A5_A5") (pintype "bidirectional"))
      (node (ref "R2-USB1") (pin "2") (pinfunction "2_2") (pintype "passive"))
    )
    (net (code "35") (name "Net-(J2-PadB5)") (class "Default")
      (node (ref "J2") (pin "B5") (pinfunction "B5_B5") (pintype "bidirectional"))
      (node (ref "R2-USB") (pin "1") (pinfunction "1_1") (pintype "passive"))
    )
    (net (code "36") (name "Net-(MCP73831-PROG)") (class "Default")
      (node (ref "MCP73831") (pin "5") (pinfunction "PROG_5") (pintype "input"))
      (node (ref "R2_BAT") (pin "2") (pinfunction "2_2") (pintype "passive"))
    )
    (net (code "37") (name "Net-(MCP73831-STAT)") (class "Default")
      (node (ref "MCP73831") (pin "1") (pinfunction "STAT_1") (pintype "output"))
      (node (ref "R1_BAT") (pin "2") (pinfunction "2_2") (pintype "passive"))
    )
    (net (code "38") (name "Net-(SENSOR2-CSB)") (class "Default")
      (node (ref "SENSOR2") (pin "2") (pinfunction "CSB_2") (pintype "input"))
      (node (ref "SENSOR2") (pin "8") (pinfunction "VDD_8") (pintype "power_in"))
    )
    (net (code "39") (name "PREVGH") (class "Default")
      (node (ref "D5") (pin "1") (pinfunction "K_1") (pintype "bidirectional"))
      (node (ref "EPD_C9") (pin "2") (pinfunction "2_2") (pintype "passive"))
      (node (ref "J1") (pin "21") (pinfunction "21_21") (pintype "bidirectional"))
    )
    (net (code "40") (name "PREVGL") (class "Default")
      (node (ref "D4") (pin "2") (pinfunction "A_2") (pintype "bidirectional"))
      (node (ref "EPD_C11") (pin "2") (pinfunction "2_2") (pintype "passive"))
      (node (ref "J1") (pin "23") (pinfunction "23_23") (pintype "bidirectional"))
    )
    (net (code "41") (name "RESE") (class "Default")
      (node (ref "J1") (pin "3") (pinfunction "3_3") (pintype "bidirectional"))
      (node (ref "Q3") (pin "2") (pinfunction "S_2") (pintype "bidirectional"))
      (node (ref "R3") (pin "2") (pinfunction "2_2") (pintype "passive"))
    )
    (net (code "42") (name "RESE'") (class "Default")
      (node (ref "R2") (pin "2") (pinfunction "2_2") (pintype "passive"))
      (node (ref "R3") (pin "1") (pinfunction "1_1") (pintype "passive"))
      (node (ref "SJ1") (pin "2") (pinfunction "2_2") (pintype "passive"))
    )
    (net (code "43") (name "RESET") (class "Default")
      (node (ref "C5") (pin "1") (pinfunction "1_1") (pintype "passive"))
      (node (ref "IC1") (pin "1") (pinfunction "VOUT_1") (pintype "bidirectional"))
      (node (ref "RESET_BUTTON") (pin "3") (pinfunction "3_3") (pintype "passive"))
      (node (ref "RESET_BUTTON") (pin "4") (pinfunction "4_4") (pintype "passive"))
      (node (ref "R_RESET") (pin "1") (pinfunction "1_1") (pintype "passive"))
      (node (ref "U2") (pin "3") (pinfunction "EN_3") (pintype "input"))
    )
    (net (code "44") (name "RTC_RST") (class "Default")
      (node (ref "U2") (pin "16") (pinfunction "IO18_16") (pintype "bidirectional"))
      (node (ref "U3") (pin "4") (pinfunction "~{RST}_4") (pintype "input"))
    )
    (net (code "45") (name "RX") (class "Default")
      (node (ref "TP2") (pin "TP") (pinfunction "TP_TP") (pintype "input"))
      (node (ref "U2") (pin "24") (pinfunction "RXD0/GPIO17_24") (pintype "bidirectional"))
    )
    (net (code "46") (name "SCK") (class "Default")
      (node (ref "D10") (pin "2") (pinfunction "2_2") (pintype "passive"))
      (node (ref "J1") (pin "13") (pinfunction "13_13") (pintype "bidirectional"))
      (node (ref "J4") (pin "P5") (pinfunction "CLK_P5") (pintype "bidirectional"))
      (node (ref "R6") (pin "1") (pinfunction "1_1") (pintype "passive"))
      (node (ref "TP8") (pin "TP") (pinfunction "TP_TP") (pintype "input"))
      (node (ref "U1") (pin "6") (pinfunction "CLK_6") (pintype "input"))
      (node (ref "U2") (pin "6") (pinfunction "IO6_6") (pintype "bidirectional"))
    )
    (net (code "47") (name "SCL") (class "Default")
      (node (ref "J3") (pin "4") (pinfunction "4_4") (pintype "passive"))
      (node (ref "R2-PINH") (pin "1") (pinfunction "1_1") (pintype "passive"))
      (node (ref "SENSOR2") (pin "4") (pinfunction "SCK_4") (pintype "input"))
      (node (ref "U2") (pin "20") (pinfunction "IO22_20") (pintype "bidirectional"))
      (node (ref "U3") (pin "16") (pinfunction "SCL_16") (pintype "input"))
      (node (ref "U4") (pin "7") (pinfunction "SCL_7") (pintype "input"))
    )
    (net (code "48") (name "SDA") (class "Default")
      (node (ref "J3") (pin "3") (pinfunction "3_3") (pintype "passive"))
      (node (ref "R1-PINH") (pin "1") (pinfunction "1_1") (pintype "passive"))
      (node (ref "SENSOR2") (pin "3") (pinfunction "SDI_3") (pintype "bidirectional"))
      (node (ref "U2") (pin "19") (pinfunction "IO21_19") (pintype "bidirectional"))
      (node (ref "U3") (pin "15") (pinfunction "SDA_15") (pintype "bidirectional"))
      (node (ref "U4") (pin "8") (pinfunction "SDA_8") (pintype "bidirectional"))
    )
    (net (code "49") (name "SRC") (class "Default")
      (node (ref "C4") (pin "2") (pinfunction "2_2") (pintype "passive"))
      (node (ref "D5") (pin "2") (pinfunction "A_2") (pintype "bidirectional"))
      (node (ref "L1") (pin "1") (pinfunction "1_1") (pintype "passive"))
      (node (ref "Q3") (pin "3") (pinfunction "D_3") (pintype "bidirectional"))
    )
    (net (code "50") (name "SS_SD") (class "Default")
      (node (ref "D8") (pin "2") (pinfunction "2_2") (pintype "passive"))
      (node (ref "J4") (pin "P2") (pinfunction "CD/DAT3_P2") (pintype "bidirectional"))
      (node (ref "R10") (pin "1") (pinfunction "1_1") (pintype "passive"))
      (node (ref "U2") (pin "4") (pinfunction "IO4_4") (pintype "bidirectional"))
    )
    (net (code "51") (name "TX") (class "Default")
      (node (ref "TP1") (pin "TP") (pinfunction "TP_TP") (pintype "input"))
      (node (ref "U2") (pin "25") (pinfunction "TXD0/GPIO16_25") (pintype "bidirectional"))
    )
    (net (code "52") (name "USB_D+") (class "Default")
      (node (ref "D1") (pin "1") (pinfunction "I/O1_1_1") (pintype "bidirectional"))
      (node (ref "U2") (pin "14") (pinfunction "IO13_14") (pintype "bidirectional"))
    )
    (net (code "53") (name "USB_D-") (class "Default")
      (node (ref "D1") (pin "3") (pinfunction "I/O2_1_3") (pintype "bidirectional"))
      (node (ref "U2") (pin "13") (pinfunction "IO12_13") (pintype "bidirectional"))
    )
    (net (code "54") (name "VBAT") (class "Default")
      (node (ref "C2_BAT") (pin "1") (pinfunction "1_1") (pintype "passive"))
      (node (ref "MCP73831") (pin "3") (pinfunction "VBAT_3") (pintype "power_in"))
      (node (ref "Q1") (pin "3") (pinfunction "D_3") (pintype "bidirectional"))
      (node (ref "TP3") (pin "TP") (pinfunction "TP_TP") (pintype "input"))
      (node (ref "U4") (pin "2") (pinfunction "CELL_2") (pintype "power_in"))
      (node (ref "U4") (pin "3") (pinfunction "VDD_3") (pintype "power_in"))
    )
    (net (code "55") (name "VBUS") (class "Default")
      (node (ref "C1_BAT") (pin "1") (pinfunction "1_1") (pintype "passive"))
      (node (ref "C4_USB") (pin "1") (pinfunction "1_1") (pintype "passive"))
      (node (ref "C5_USB") (pin "1") (pinfunction "1_1") (pintype "passive"))
      (node (ref "CHG_LED") (pin "A") (pinfunction "A_A") (pintype "passive"))
      (node (ref "D1") (pin "5") (pinfunction "VBUS_5") (pintype "bidirectional"))
      (node (ref "MCP73831") (pin "4") (pinfunction "VIN_4") (pintype "power_in"))
      (node (ref "PFMF.050.1") (pin "2") (pinfunction "2_2") (pintype "passive"))
      (node (ref "TP14") (pin "TP") (pinfunction "TP_TP") (pintype "input"))
    )
    (net (code "56") (name "VRTC") (class "Default")
      (node (ref "C10_SUPERCAP") (pin "2") (pinfunction "2_2") (pintype "passive"))
      (node (ref "C8") (pin "1") (pinfunction "1_1") (pintype "passive"))
      (node (ref "R_CAPACITOR") (pin "2") (pinfunction "2_2") (pintype "passive"))
      (node (ref "U3") (pin "14") (pinfunction "VBAT_14") (pintype "power_in"))
    )
    (net (code "57") (name "VUSB") (class "Default")
      (node (ref "J2") (pin "A4") (pinfunction "A4_A4") (pintype "bidirectional"))
      (node (ref "J2") (pin "A9") (pinfunction "A9_A9") (pintype "bidirectional"))
      (node (ref "J2") (pin "B4") (pinfunction "B4_B4") (pintype "bidirectional"))
      (node (ref "J2") (pin "B9") (pinfunction "B9_B9") (pintype "bidirectional"))
      (node (ref "PFMF.050.1") (pin "1") (pinfunction "1_1") (pintype "passive"))
    )
    (net (code "58") (name "unconnected-(IC1-NC-Pad4)") (class "Default")
      (node (ref "IC1") (pin "4") (pinfunction "NC_4") (pintype "no_connect"))
    )
    (net (code "59") (name "unconnected-(IC4-NC-Pad4)") (class "Default")
      (node (ref "IC4") (pin "4") (pinfunction "NC_4") (pintype "no_connect"))
    )
    (net (code "60") (name "unconnected-(J1-Pad1)") (class "Default")
      (node (ref "J1") (pin "1") (pinfunction "1_1") (pintype "bidirectional"))
    )
    (net (code "61") (name "unconnected-(J1-Pad6)") (class "Default")
      (node (ref "J1") (pin "6") (pinfunction "6_6") (pintype "bidirectional"))
    )
    (net (code "62") (name "unconnected-(J1-Pad7)") (class "Default")
      (node (ref "J1") (pin "7") (pinfunction "7_7") (pintype "bidirectional"))
    )
    (net (code "63") (name "unconnected-(J2-PadA8)") (class "Default")
      (node (ref "J2") (pin "A8") (pinfunction "A8_A8") (pintype "bidirectional"))
    )
    (net (code "64") (name "unconnected-(J2-PadB8)") (class "Default")
      (node (ref "J2") (pin "B8") (pinfunction "B8_B8") (pintype "bidirectional"))
    )
    (net (code "65") (name "unconnected-(J4-DAT1-PadP8)") (class "Default")
      (node (ref "J4") (pin "P8") (pinfunction "DAT1_P8") (pintype "bidirectional"))
    )
    (net (code "66") (name "unconnected-(J4-DAT2-PadP1)") (class "Default")
      (node (ref "J4") (pin "P1") (pinfunction "DAT2_P1") (pintype "bidirectional"))
    )
    (net (code "67") (name "unconnected-(J4-DETECTION_1-PadS1)") (class "Default")
      (node (ref "J4") (pin "S1") (pinfunction "DETECTION_1_S1") (pintype "bidirectional"))
    )
    (net (code "68") (name "unconnected-(J4-DETECTION_2-PadS2)") (class "Default")
      (node (ref "J4") (pin "S2") (pinfunction "DETECTION_2_S2") (pintype "bidirectional"))
    )
    (net (code "69") (name "unconnected-(U2-NC-Pad22)") (class "Default")
      (node (ref "U2") (pin "22") (pinfunction "NC_22") (pintype "no_connect"))
    )
    (net (code "70") (name "unconnected-(U4-~{ALERT}-Pad5)") (class "Default")
      (node (ref "U4") (pin "5") (pinfunction "~{ALERT}_5") (pintype "output"))
    )
  )
)
